# tvbgone.net
KiCad netlist of a schematic drawn in EAGLE
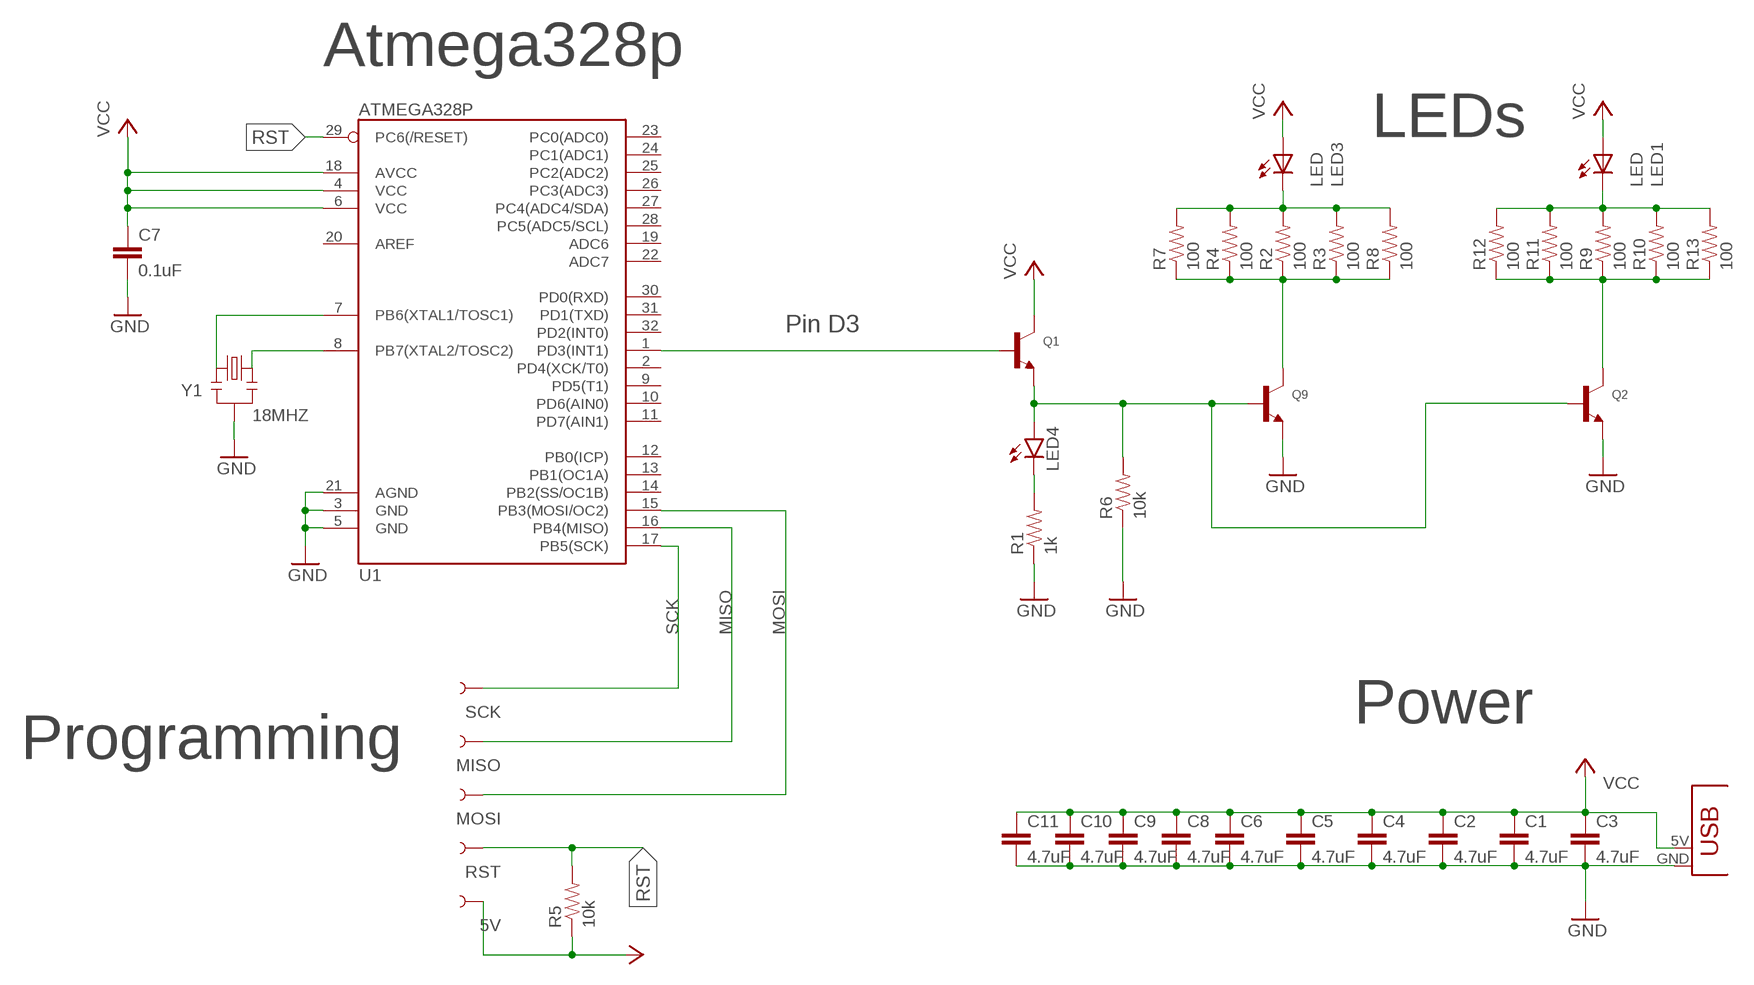
[diagram p0: schematic, sheet 1]

(export (version "E")
  (design (tool "Eeschema 10.0.6"))
  (components
    (comp (ref "5V")
      (value "TEST-POINT3X5")
      (footprint "eagle-import:PAD.03X.05")
      (libsource (lib "eagle-import") (part "TEST-POINT3X5"))
    )
    (comp (ref "C1")
      (value "4.7uF")
      (footprint "eagle-import:0603-CAP")
      (libsource (lib "eagle-import") (part "CAP0603-CAP"))
    )
    (comp (ref "C2")
      (value "4.7uF")
      (footprint "eagle-import:0603-CAP")
      (libsource (lib "eagle-import") (part "CAP0603-CAP"))
    )
    (comp (ref "C3")
      (value "4.7uF")
      (footprint "eagle-import:0603-CAP")
      (libsource (lib "eagle-import") (part "CAP0603-CAP"))
    )
    (comp (ref "C4")
      (value "4.7uF")
      (footprint "eagle-import:0603-CAP")
      (libsource (lib "eagle-import") (part "CAP0603-CAP"))
    )
    (comp (ref "C5")
      (value "4.7uF")
      (footprint "eagle-import:0603-CAP")
      (libsource (lib "eagle-import") (part "CAP0603-CAP"))
    )
    (comp (ref "C6")
      (value "4.7uF")
      (footprint "eagle-import:0603-CAP")
      (libsource (lib "eagle-import") (part "CAP0603-CAP"))
    )
    (comp (ref "C7")
      (value "0.1uF")
      (footprint "eagle-import:0603-CAP")
      (libsource (lib "eagle-import") (part "CAP0603-CAP"))
    )
    (comp (ref "C8")
      (value "4.7uF")
      (footprint "eagle-import:0603-CAP")
      (libsource (lib "eagle-import") (part "CAP0603-CAP"))
    )
    (comp (ref "C9")
      (value "4.7uF")
      (footprint "eagle-import:0603-CAP")
      (libsource (lib "eagle-import") (part "CAP0603-CAP"))
    )
    (comp (ref "C10")
      (value "4.7uF")
      (footprint "eagle-import:0603-CAP")
      (libsource (lib "eagle-import") (part "CAP0603-CAP"))
    )
    (comp (ref "C11")
      (value "4.7uF")
      (footprint "eagle-import:0603-CAP")
      (libsource (lib "eagle-import") (part "CAP0603-CAP"))
    )
    (comp (ref "LED1")
      (value "LED")
      (footprint "eagle-import:5MM-SIDE")
      (libsource (lib "eagle-import") (part "LED"))
    )
    (comp (ref "LED3")
      (value "LED")
      (footprint "eagle-import:5MM-SIDE")
      (libsource (lib "eagle-import") (part "LED"))
    )
    (comp (ref "LED4")
      (value "LED0603")
      (footprint "eagle-import:LED-0603")
      (libsource (lib "eagle-import") (part "LED0603"))
    )
    (comp (ref "MISO")
      (value "TEST-POINT3X5")
      (footprint "eagle-import:PAD.03X.05")
      (libsource (lib "eagle-import") (part "TEST-POINT3X5"))
    )
    (comp (ref "MOSI")
      (value "TEST-POINT3X5")
      (footprint "eagle-import:PAD.03X.05")
      (libsource (lib "eagle-import") (part "TEST-POINT3X5"))
    )
    (comp (ref "Q1")
      (value "TRANSISTOR_NPN")
      (footprint "eagle-import:SOT-23-R")
      (libsource (lib "eagle-import") (part "TRANSISTOR_NPN"))
    )
    (comp (ref "Q2")
      (value "TRANSISTOR_NPN")
      (footprint "eagle-import:SOT-23-R")
      (libsource (lib "eagle-import") (part "TRANSISTOR_NPN"))
    )
    (comp (ref "Q9")
      (value "TRANSISTOR_NPN")
      (footprint "eagle-import:SOT-23-R")
      (libsource (lib "eagle-import") (part "TRANSISTOR_NPN"))
    )
    (comp (ref "R1")
      (value "1k")
      (footprint "eagle-import:0603-RES")
      (libsource (lib "eagle-import") (part "RESISTOR0603"))
    )
    (comp (ref "R2")
      (value "100")
      (footprint "eagle-import:0603-RES")
      (libsource (lib "eagle-import") (part "RESISTOR0603"))
    )
    (comp (ref "R3")
      (value "100")
      (footprint "eagle-import:0603-RES")
      (libsource (lib "eagle-import") (part "RESISTOR0603"))
    )
    (comp (ref "R4")
      (value "100")
      (footprint "eagle-import:0603-RES")
      (libsource (lib "eagle-import") (part "RESISTOR0603"))
    )
    (comp (ref "R5")
      (value "10k")
      (footprint "eagle-import:0603-RES")
      (libsource (lib "eagle-import") (part "RESISTOR0603"))
    )
    (comp (ref "R6")
      (value "10k")
      (footprint "eagle-import:0603-RES")
      (libsource (lib "eagle-import") (part "RESISTOR0603"))
    )
    (comp (ref "R7")
      (value "100")
      (footprint "eagle-import:0603-RES")
      (libsource (lib "eagle-import") (part "RESISTOR0603"))
    )
    (comp (ref "R8")
      (value "100")
      (footprint "eagle-import:0603-RES")
      (libsource (lib "eagle-import") (part "RESISTOR0603"))
    )
    (comp (ref "R9")
      (value "100")
      (footprint "eagle-import:0603-RES")
      (libsource (lib "eagle-import") (part "RESISTOR0603"))
    )
    (comp (ref "R10")
      (value "100")
      (footprint "eagle-import:0603-RES")
      (libsource (lib "eagle-import") (part "RESISTOR0603"))
    )
    (comp (ref "R11")
      (value "100")
      (footprint "eagle-import:0603-RES")
      (libsource (lib "eagle-import") (part "RESISTOR0603"))
    )
    (comp (ref "R12")
      (value "100")
      (footprint "eagle-import:0603-RES")
      (libsource (lib "eagle-import") (part "RESISTOR0603"))
    )
    (comp (ref "R13")
      (value "100")
      (footprint "eagle-import:0603-RES")
      (libsource (lib "eagle-import") (part "RESISTOR0603"))
    )
    (comp (ref "RST")
      (value "TEST-POINT3X5")
      (footprint "eagle-import:PAD.03X.05")
      (libsource (lib "eagle-import") (part "TEST-POINT3X5"))
    )
    (comp (ref "SCK")
      (value "TEST-POINT3X5")
      (footprint "eagle-import:PAD.03X.05")
      (libsource (lib "eagle-import") (part "TEST-POINT3X5"))
    )
    (comp (ref "U$1")
      (value "USB-POWER-ONLY")
      (footprint "eagle-import:USB-A-PCB-POWER-ONLY")
      (libsource (lib "eagle-import") (part "USB-POWER-ONLY"))
    )
    (comp (ref "U1")
      (value "ATMEGA328P")
      (footprint "eagle-import:TQFP32-08")
      (libsource (lib "eagle-import") (part "ATMEGA328_SMT"))
    )
    (comp (ref "Y1")
      (value "18MHZ")
      (footprint "eagle-import:RESONATOR-SMD")
      (libsource (lib "eagle-import") (part "RESONATOR8MHZ"))
    )
  )
  (nets
    (net (code "1") (name "/MISO") (class "Default")
      (node (ref "MISO") (pin "P$1") (pinfunction "1_P$1") (pintype "bidirectional"))
      (node (ref "U1") (pin "16") (pinfunction "PB4(MISO)_16") (pintype "bidirectional"))
    )
    (net (code "2") (name "/MOSI") (class "Default")
      (node (ref "MOSI") (pin "P$1") (pinfunction "1_P$1") (pintype "bidirectional"))
      (node (ref "U1") (pin "15") (pinfunction "PB3(MOSI/OC2)_15") (pintype "bidirectional"))
    )
    (net (code "3") (name "/SCK") (class "Default")
      (node (ref "SCK") (pin "P$1") (pinfunction "1_P$1") (pintype "bidirectional"))
      (node (ref "U1") (pin "17") (pinfunction "PB5(SCK)_17") (pintype "bidirectional"))
    )
    (net (code "4") (name "GND") (class "Default")
      (node (ref "C1") (pin "2") (pinfunction "2_2") (pintype "passive"))
      (node (ref "C10") (pin "2") (pinfunction "2_2") (pintype "passive"))
      (node (ref "C11") (pin "2") (pinfunction "2_2") (pintype "passive"))
      (node (ref "C2") (pin "2") (pinfunction "2_2") (pintype "passive"))
      (node (ref "C3") (pin "2") (pinfunction "2_2") (pintype "passive"))
      (node (ref "C4") (pin "2") (pinfunction "2_2") (pintype "passive"))
      (node (ref "C5") (pin "2") (pinfunction "2_2") (pintype "passive"))
      (node (ref "C6") (pin "2") (pinfunction "2_2") (pintype "passive"))
      (node (ref "C7") (pin "2") (pinfunction "2_2") (pintype "passive"))
      (node (ref "C8") (pin "2") (pinfunction "2_2") (pintype "passive"))
      (node (ref "C9") (pin "2") (pinfunction "2_2") (pintype "passive"))
      (node (ref "Q2") (pin "3-EMITTER") (pinfunction "E_3-EMITTER") (pintype "passive"))
      (node (ref "Q9") (pin "3-EMITTER") (pinfunction "E_3-EMITTER") (pintype "passive"))
      (node (ref "R1") (pin "1") (pinfunction "1_1") (pintype "passive"))
      (node (ref "R6") (pin "1") (pinfunction "1_1") (pintype "passive"))
      (node (ref "U$1") (pin "GND") (pinfunction "GND_GND") (pintype "bidirectional"))
      (node (ref "U1") (pin "21") (pinfunction "AGND_21") (pintype "bidirectional"))
      (node (ref "U1") (pin "3") (pinfunction "GND_3") (pintype "bidirectional"))
      (node (ref "U1") (pin "5") (pinfunction "GND_5") (pintype "bidirectional"))
      (node (ref "Y1") (pin "2") (pinfunction "2_2") (pintype "passive"))
    )
    (net (code "5") (name "Net-(LED1-C)") (class "Default")
      (node (ref "LED1") (pin "K") (pinfunction "C_K") (pintype "passive"))
      (node (ref "R10") (pin "2") (pinfunction "2_2") (pintype "passive"))
      (node (ref "R11") (pin "2") (pinfunction "2_2") (pintype "passive"))
      (node (ref "R12") (pin "2") (pinfunction "2_2") (pintype "passive"))
      (node (ref "R13") (pin "2") (pinfunction "2_2") (pintype "passive"))
      (node (ref "R9") (pin "2") (pinfunction "2_2") (pintype "passive"))
    )
    (net (code "6") (name "Net-(LED3-C)") (class "Default")
      (node (ref "LED3") (pin "K") (pinfunction "C_K") (pintype "passive"))
      (node (ref "R2") (pin "2") (pinfunction "2_2") (pintype "passive"))
      (node (ref "R3") (pin "2") (pinfunction "2_2") (pintype "passive"))
      (node (ref "R4") (pin "2") (pinfunction "2_2") (pintype "passive"))
      (node (ref "R7") (pin "2") (pinfunction "2_2") (pintype "passive"))
      (node (ref "R8") (pin "2") (pinfunction "2_2") (pintype "passive"))
    )
    (net (code "7") (name "Net-(LED4-PadC)") (class "Default")
      (node (ref "LED4") (pin "C") (pinfunction "C_C") (pintype "passive"))
      (node (ref "R1") (pin "2") (pinfunction "2_2") (pintype "passive"))
    )
    (net (code "8") (name "Net-(Q1-B)") (class "Default")
      (node (ref "Q1") (pin "1-BASE") (pinfunction "B_1-BASE") (pintype "passive"))
      (node (ref "U1") (pin "1") (pinfunction "PD3(INT1)_1") (pintype "bidirectional"))
    )
    (net (code "9") (name "Net-(Q1-E)") (class "Default")
      (node (ref "LED4") (pin "A") (pinfunction "A_A") (pintype "passive"))
      (node (ref "Q1") (pin "3-EMITTER") (pinfunction "E_3-EMITTER") (pintype "passive"))
      (node (ref "Q2") (pin "1-BASE") (pinfunction "B_1-BASE") (pintype "passive"))
      (node (ref "Q9") (pin "1-BASE") (pinfunction "B_1-BASE") (pintype "passive"))
      (node (ref "R6") (pin "2") (pinfunction "2_2") (pintype "passive"))
    )
    (net (code "10") (name "Net-(Q2-C)") (class "Default")
      (node (ref "Q2") (pin "2-COLLECTOR") (pinfunction "C_2-COLLECTOR") (pintype "passive"))
      (node (ref "R10") (pin "1") (pinfunction "1_1") (pintype "passive"))
      (node (ref "R11") (pin "1") (pinfunction "1_1") (pintype "passive"))
      (node (ref "R12") (pin "1") (pinfunction "1_1") (pintype "passive"))
      (node (ref "R13") (pin "1") (pinfunction "1_1") (pintype "passive"))
      (node (ref "R9") (pin "1") (pinfunction "1_1") (pintype "passive"))
    )
    (net (code "11") (name "Net-(Q9-C)") (class "Default")
      (node (ref "Q9") (pin "2-COLLECTOR") (pinfunction "C_2-COLLECTOR") (pintype "passive"))
      (node (ref "R2") (pin "1") (pinfunction "1_1") (pintype "passive"))
      (node (ref "R3") (pin "1") (pinfunction "1_1") (pintype "passive"))
      (node (ref "R4") (pin "1") (pinfunction "1_1") (pintype "passive"))
      (node (ref "R7") (pin "1") (pinfunction "1_1") (pintype "passive"))
      (node (ref "R8") (pin "1") (pinfunction "1_1") (pintype "passive"))
    )
    (net (code "12") (name "Net-(U1-PB6(XTAL1{slash}TOSC1))") (class "Default")
      (node (ref "U1") (pin "7") (pinfunction "PB6(XTAL1/TOSC1)_7") (pintype "bidirectional"))
      (node (ref "Y1") (pin "1") (pinfunction "1_1") (pintype "passive"))
    )
    (net (code "13") (name "Net-(U1-PB7(XTAL2{slash}TOSC2))") (class "Default")
      (node (ref "U1") (pin "8") (pinfunction "PB7(XTAL2/TOSC2)_8") (pintype "bidirectional"))
      (node (ref "Y1") (pin "3") (pinfunction "3_3") (pintype "passive"))
    )
    (net (code "14") (name "RST") (class "Default")
      (node (ref "R5") (pin "2") (pinfunction "2_2") (pintype "passive"))
      (node (ref "RST") (pin "P$1") (pinfunction "1_P$1") (pintype "bidirectional"))
      (node (ref "U1") (pin "29") (pinfunction "PC6(/RESET)_29") (pintype "bidirectional"))
    )
    (net (code "15") (name "VCC") (class "Default")
      (node (ref "5V") (pin "P$1") (pinfunction "1_P$1") (pintype "bidirectional"))
      (node (ref "C1") (pin "1") (pinfunction "1_1") (pintype "passive"))
      (node (ref "C10") (pin "1") (pinfunction "1_1") (pintype "passive"))
      (node (ref "C11") (pin "1") (pinfunction "1_1") (pintype "passive"))
      (node (ref "C2") (pin "1") (pinfunction "1_1") (pintype "passive"))
      (node (ref "C3") (pin "1") (pinfunction "1_1") (pintype "passive"))
      (node (ref "C4") (pin "1") (pinfunction "1_1") (pintype "passive"))
      (node (ref "C5") (pin "1") (pinfunction "1_1") (pintype "passive"))
      (node (ref "C6") (pin "1") (pinfunction "1_1") (pintype "passive"))
      (node (ref "C7") (pin "1") (pinfunction "1_1") (pintype "passive"))
      (node (ref "C8") (pin "1") (pinfunction "1_1") (pintype "passive"))
      (node (ref "C9") (pin "1") (pinfunction "1_1") (pintype "passive"))
      (node (ref "LED1") (pin "A") (pinfunction "A_A") (pintype "passive"))
      (node (ref "LED3") (pin "A") (pinfunction "A_A") (pintype "passive"))
      (node (ref "Q1") (pin "2-COLLECTOR") (pinfunction "C_2-COLLECTOR") (pintype "passive"))
      (node (ref "R5") (pin "1") (pinfunction "1_1") (pintype "passive"))
      (node (ref "U$1") (pin "5V") (pinfunction "VBUS_5V") (pintype "bidirectional"))
      (node (ref "U1") (pin "18") (pinfunction "AVCC_18") (pintype "bidirectional"))
      (node (ref "U1") (pin "4") (pinfunction "VCC_4") (pintype "bidirectional"))
      (node (ref "U1") (pin "6") (pinfunction "VCC_6") (pintype "bidirectional"))
    )
    (net (code "16") (name "unconnected-(U1-ADC6-Pad19)") (class "Default")
      (node (ref "U1") (pin "19") (pinfunction "ADC6_19") (pintype "bidirectional"))
    )
    (net (code "17") (name "unconnected-(U1-ADC7-Pad22)") (class "Default")
      (node (ref "U1") (pin "22") (pinfunction "ADC7_22") (pintype "bidirectional"))
    )
    (net (code "18") (name "unconnected-(U1-AREF-Pad20)") (class "Default")
      (node (ref "U1") (pin "20") (pinfunction "AREF_20") (pintype "bidirectional"))
    )
    (net (code "19") (name "unconnected-(U1-PB0(ICP)-Pad12)") (class "Default")
      (node (ref "U1") (pin "12") (pinfunction "PB0(ICP)_12") (pintype "bidirectional"))
    )
    (net (code "20") (name "unconnected-(U1-PB1(OC1A)-Pad13)") (class "Default")
      (node (ref "U1") (pin "13") (pinfunction "PB1(OC1A)_13") (pintype "bidirectional"))
    )
    (net (code "21") (name "unconnected-(U1-PB2(SS{slash}OC1B)-Pad14)") (class "Default")
      (node (ref "U1") (pin "14") (pinfunction "PB2(SS/OC1B)_14") (pintype "bidirectional"))
    )
    (net (code "22") (name "unconnected-(U1-PC0(ADC0)-Pad23)") (class "Default")
      (node (ref "U1") (pin "23") (pinfunction "PC0(ADC0)_23") (pintype "bidirectional"))
    )
    (net (code "23") (name "unconnected-(U1-PC1(ADC1)-Pad24)") (class "Default")
      (node (ref "U1") (pin "24") (pinfunction "PC1(ADC1)_24") (pintype "bidirectional"))
    )
    (net (code "24") (name "unconnected-(U1-PC2(ADC2)-Pad25)") (class "Default")
      (node (ref "U1") (pin "25") (pinfunction "PC2(ADC2)_25") (pintype "bidirectional"))
    )
    (net (code "25") (name "unconnected-(U1-PC3(ADC3)-Pad26)") (class "Default")
      (node (ref "U1") (pin "26") (pinfunction "PC3(ADC3)_26") (pintype "bidirectional"))
    )
    (net (code "26") (name "unconnected-(U1-PC4(ADC4{slash}SDA)-Pad27)") (class "Default")
      (node (ref "U1") (pin "27") (pinfunction "PC4(ADC4/SDA)_27") (pintype "bidirectional"))
    )
    (net (code "27") (name "unconnected-(U1-PC5(ADC5{slash}SCL)-Pad28)") (class "Default")
      (node (ref "U1") (pin "28") (pinfunction "PC5(ADC5/SCL)_28") (pintype "bidirectional"))
    )
    (net (code "28") (name "unconnected-(U1-PD0(RXD)-Pad30)") (class "Default")
      (node (ref "U1") (pin "30") (pinfunction "PD0(RXD)_30") (pintype "bidirectional"))
    )
    (net (code "29") (name "unconnected-(U1-PD1(TXD)-Pad31)") (class "Default")
      (node (ref "U1") (pin "31") (pinfunction "PD1(TXD)_31") (pintype "bidirectional"))
    )
    (net (code "30") (name "unconnected-(U1-PD2(INT0)-Pad32)") (class "Default")
      (node (ref "U1") (pin "32") (pinfunction "PD2(INT0)_32") (pintype "bidirectional"))
    )
    (net (code "31") (name "unconnected-(U1-PD4(XCK{slash}T0)-Pad2)") (class "Default")
      (node (ref "U1") (pin "2") (pinfunction "PD4(XCK/T0)_2") (pintype "bidirectional"))
    )
    (net (code "32") (name "unconnected-(U1-PD5(T1)-Pad9)") (class "Default")
      (node (ref "U1") (pin "9") (pinfunction "PD5(T1)_9") (pintype "bidirectional"))
    )
    (net (code "33") (name "unconnected-(U1-PD6(AIN0)-Pad10)") (class "Default")
      (node (ref "U1") (pin "10") (pinfunction "PD6(AIN0)_10") (pintype "bidirectional"))
    )
    (net (code "34") (name "unconnected-(U1-PD7(AIN1)-Pad11)") (class "Default")
      (node (ref "U1") (pin "11") (pinfunction "PD7(AIN1)_11") (pintype "bidirectional"))
    )
  )
)
